# Testkit.net
KiCad netlist of a schematic drawn in Altium Designer
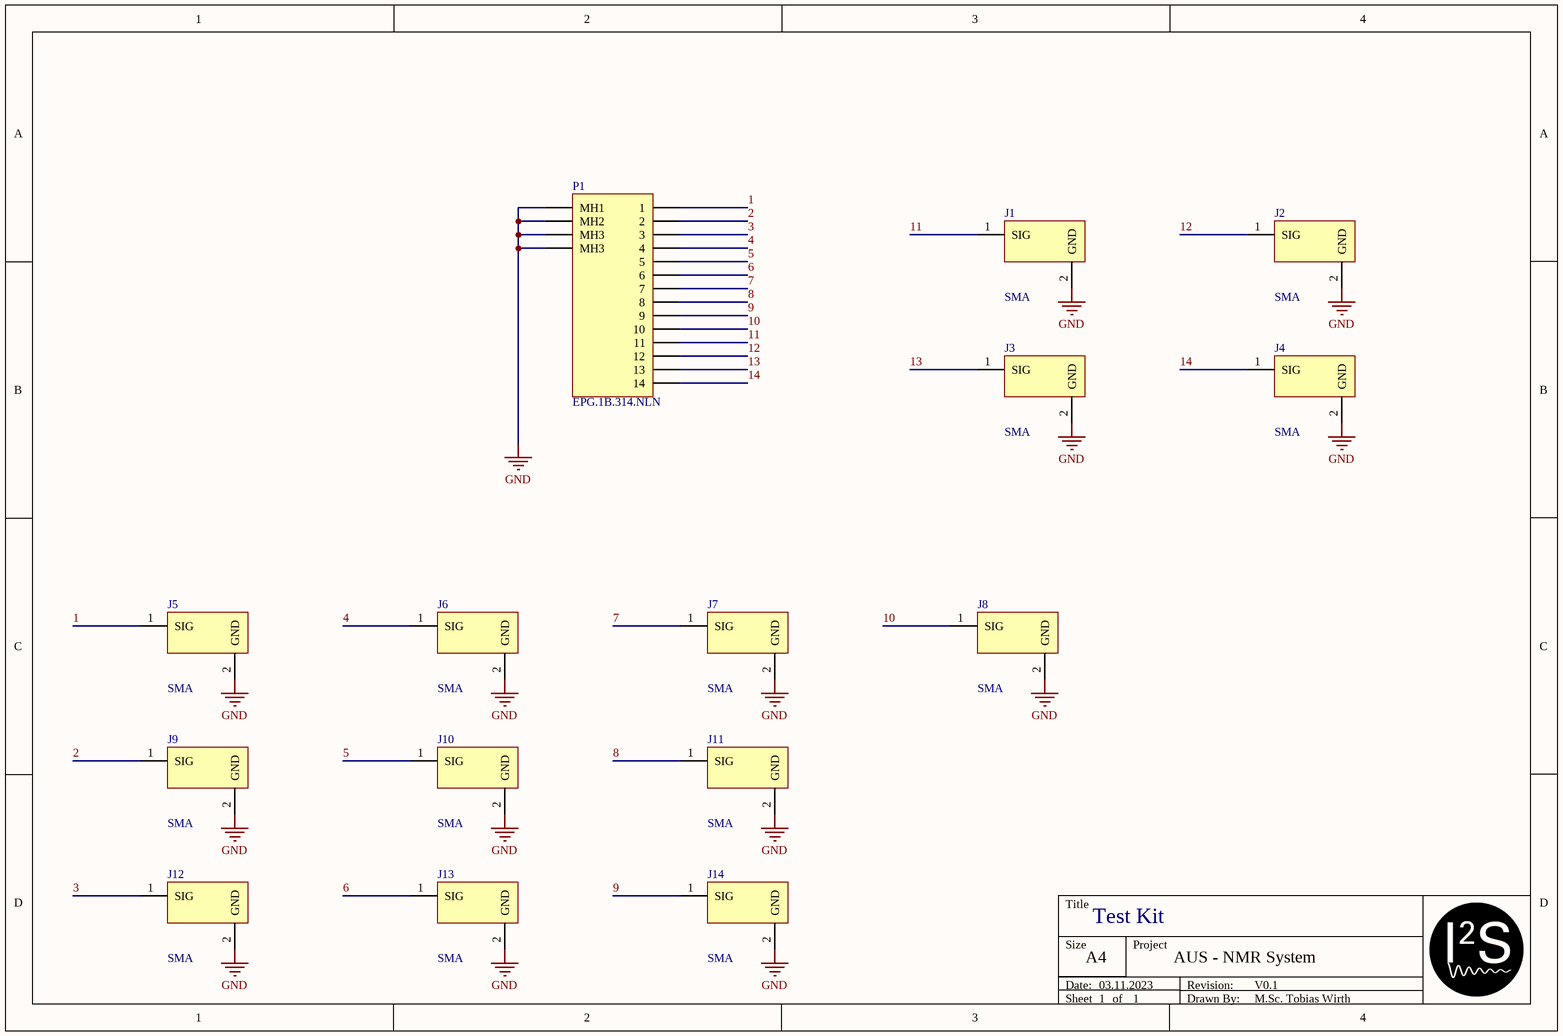
[diagram p0: Testkit.SchDoc]

(export (version "E")
  (design (tool "Eeschema 10.0.6"))
  (components
    (comp (ref "J1") (value "SMA") (footprint "SMA") (libsource (lib "IIS-Lib_TW") (part "SMA")))
    (comp (ref "J2") (value "SMA") (footprint "SMA") (libsource (lib "IIS-Lib_TW") (part "SMA")))
    (comp (ref "J3") (value "SMA") (footprint "SMA") (libsource (lib "IIS-Lib_TW") (part "SMA")))
    (comp (ref "J4") (value "SMA") (footprint "SMA") (libsource (lib "IIS-Lib_TW") (part "SMA")))
    (comp (ref "J5") (value "SMA") (footprint "SMA") (libsource (lib "IIS-Lib_TW") (part "SMA")))
    (comp (ref "J6") (value "SMA") (footprint "SMA") (libsource (lib "IIS-Lib_TW") (part "SMA")))
    (comp (ref "J7") (value "SMA") (footprint "SMA") (libsource (lib "IIS-Lib_TW") (part "SMA")))
    (comp (ref "J8") (value "SMA") (footprint "SMA") (libsource (lib "IIS-Lib_TW") (part "SMA")))
    (comp (ref "J9") (value "SMA") (footprint "SMA") (libsource (lib "IIS-Lib_TW") (part "SMA")))
    (comp (ref "J10") (value "SMA") (footprint "SMA") (libsource (lib "IIS-Lib_TW") (part "SMA")))
    (comp (ref "J11") (value "SMA") (footprint "SMA") (libsource (lib "IIS-Lib_TW") (part "SMA")))
    (comp (ref "J12") (value "SMA") (footprint "SMA") (libsource (lib "IIS-Lib_TW") (part "SMA")))
    (comp (ref "J13") (value "SMA") (footprint "SMA") (libsource (lib "IIS-Lib_TW") (part "SMA")))
    (comp (ref "J14") (value "SMA") (footprint "SMA") (libsource (lib "IIS-Lib_TW") (part "SMA")))
    (comp (ref "P1")
      (value "EPG.1B.314.NLN")
      (footprint "EPG.1B.314.NLN")
      (libsource (lib "IIS-Lib_TW") (part "EPG.1B.314.NLN"))
    )
  )
  (nets
    (net (code "1") (name "/1") (class "Default")
      (node (ref "J5") (pin "1") (pinfunction "SIG_1") (pintype "passive"))
      (node (ref "P1") (pin "1") (pinfunction "1_1") (pintype "passive"))
    )
    (net (code "2") (name "/2") (class "Default")
      (node (ref "J9") (pin "1") (pinfunction "SIG_1") (pintype "passive"))
      (node (ref "P1") (pin "2") (pinfunction "2_2") (pintype "passive"))
    )
    (net (code "3") (name "/3") (class "Default")
      (node (ref "J12") (pin "1") (pinfunction "SIG_1") (pintype "passive"))
      (node (ref "P1") (pin "3") (pinfunction "3_3") (pintype "passive"))
    )
    (net (code "4") (name "/4") (class "Default")
      (node (ref "J6") (pin "1") (pinfunction "SIG_1") (pintype "passive"))
      (node (ref "P1") (pin "4") (pinfunction "4_4") (pintype "passive"))
    )
    (net (code "5") (name "/5") (class "Default")
      (node (ref "J10") (pin "1") (pinfunction "SIG_1") (pintype "passive"))
      (node (ref "P1") (pin "5") (pinfunction "5_5") (pintype "passive"))
    )
    (net (code "6") (name "/6") (class "Default")
      (node (ref "J13") (pin "1") (pinfunction "SIG_1") (pintype "passive"))
      (node (ref "P1") (pin "6") (pinfunction "6_6") (pintype "passive"))
    )
    (net (code "7") (name "/7") (class "Default")
      (node (ref "J7") (pin "1") (pinfunction "SIG_1") (pintype "passive"))
      (node (ref "P1") (pin "7") (pinfunction "7_7") (pintype "passive"))
    )
    (net (code "8") (name "/8") (class "Default")
      (node (ref "J11") (pin "1") (pinfunction "SIG_1") (pintype "passive"))
      (node (ref "P1") (pin "8") (pinfunction "8_8") (pintype "passive"))
    )
    (net (code "9") (name "/9") (class "Default")
      (node (ref "J14") (pin "1") (pinfunction "SIG_1") (pintype "passive"))
      (node (ref "P1") (pin "9") (pinfunction "9_9") (pintype "passive"))
    )
    (net (code "10") (name "/10") (class "Default")
      (node (ref "J8") (pin "1") (pinfunction "SIG_1") (pintype "passive"))
      (node (ref "P1") (pin "10") (pinfunction "10_10") (pintype "passive"))
    )
    (net (code "11") (name "/11") (class "Default")
      (node (ref "J1") (pin "1") (pinfunction "SIG_1") (pintype "passive"))
      (node (ref "P1") (pin "11") (pinfunction "11_11") (pintype "passive"))
    )
    (net (code "12") (name "/12") (class "Default")
      (node (ref "J2") (pin "1") (pinfunction "SIG_1") (pintype "passive"))
      (node (ref "P1") (pin "12") (pinfunction "12_12") (pintype "passive"))
    )
    (net (code "13") (name "/13") (class "Default")
      (node (ref "J3") (pin "1") (pinfunction "SIG_1") (pintype "passive"))
      (node (ref "P1") (pin "13") (pinfunction "13_13") (pintype "passive"))
    )
    (net (code "14") (name "/14") (class "Default")
      (node (ref "J4") (pin "1") (pinfunction "SIG_1") (pintype "passive"))
      (node (ref "P1") (pin "14") (pinfunction "14_14") (pintype "passive"))
    )
    (net (code "15") (name "GND") (class "Default")
      (node (ref "J1") (pin "2") (pinfunction "GND_2") (pintype "passive"))
      (node (ref "J10") (pin "2") (pinfunction "GND_2") (pintype "passive"))
      (node (ref "J11") (pin "2") (pinfunction "GND_2") (pintype "passive"))
      (node (ref "J12") (pin "2") (pinfunction "GND_2") (pintype "passive"))
      (node (ref "J13") (pin "2") (pinfunction "GND_2") (pintype "passive"))
      (node (ref "J14") (pin "2") (pinfunction "GND_2") (pintype "passive"))
      (node (ref "J2") (pin "2") (pinfunction "GND_2") (pintype "passive"))
      (node (ref "J3") (pin "2") (pinfunction "GND_2") (pintype "passive"))
      (node (ref "J4") (pin "2") (pinfunction "GND_2") (pintype "passive"))
      (node (ref "J5") (pin "2") (pinfunction "GND_2") (pintype "passive"))
      (node (ref "J6") (pin "2") (pinfunction "GND_2") (pintype "passive"))
      (node (ref "J7") (pin "2") (pinfunction "GND_2") (pintype "passive"))
      (node (ref "J8") (pin "2") (pinfunction "GND_2") (pintype "passive"))
      (node (ref "J9") (pin "2") (pinfunction "GND_2") (pintype "passive"))
      (node (ref "P1") (pin "15") (pinfunction "MH1_15") (pintype "passive"))
      (node (ref "P1") (pin "16") (pinfunction "MH2_16") (pintype "passive"))
      (node (ref "P1") (pin "17") (pinfunction "MH3_17") (pintype "passive"))
      (node (ref "P1") (pin "18") (pinfunction "MH3_18") (pintype "passive"))
    )
  )
)
